# CSR8635-V1_3.net
KiCad netlist of a schematic drawn in EAGLE
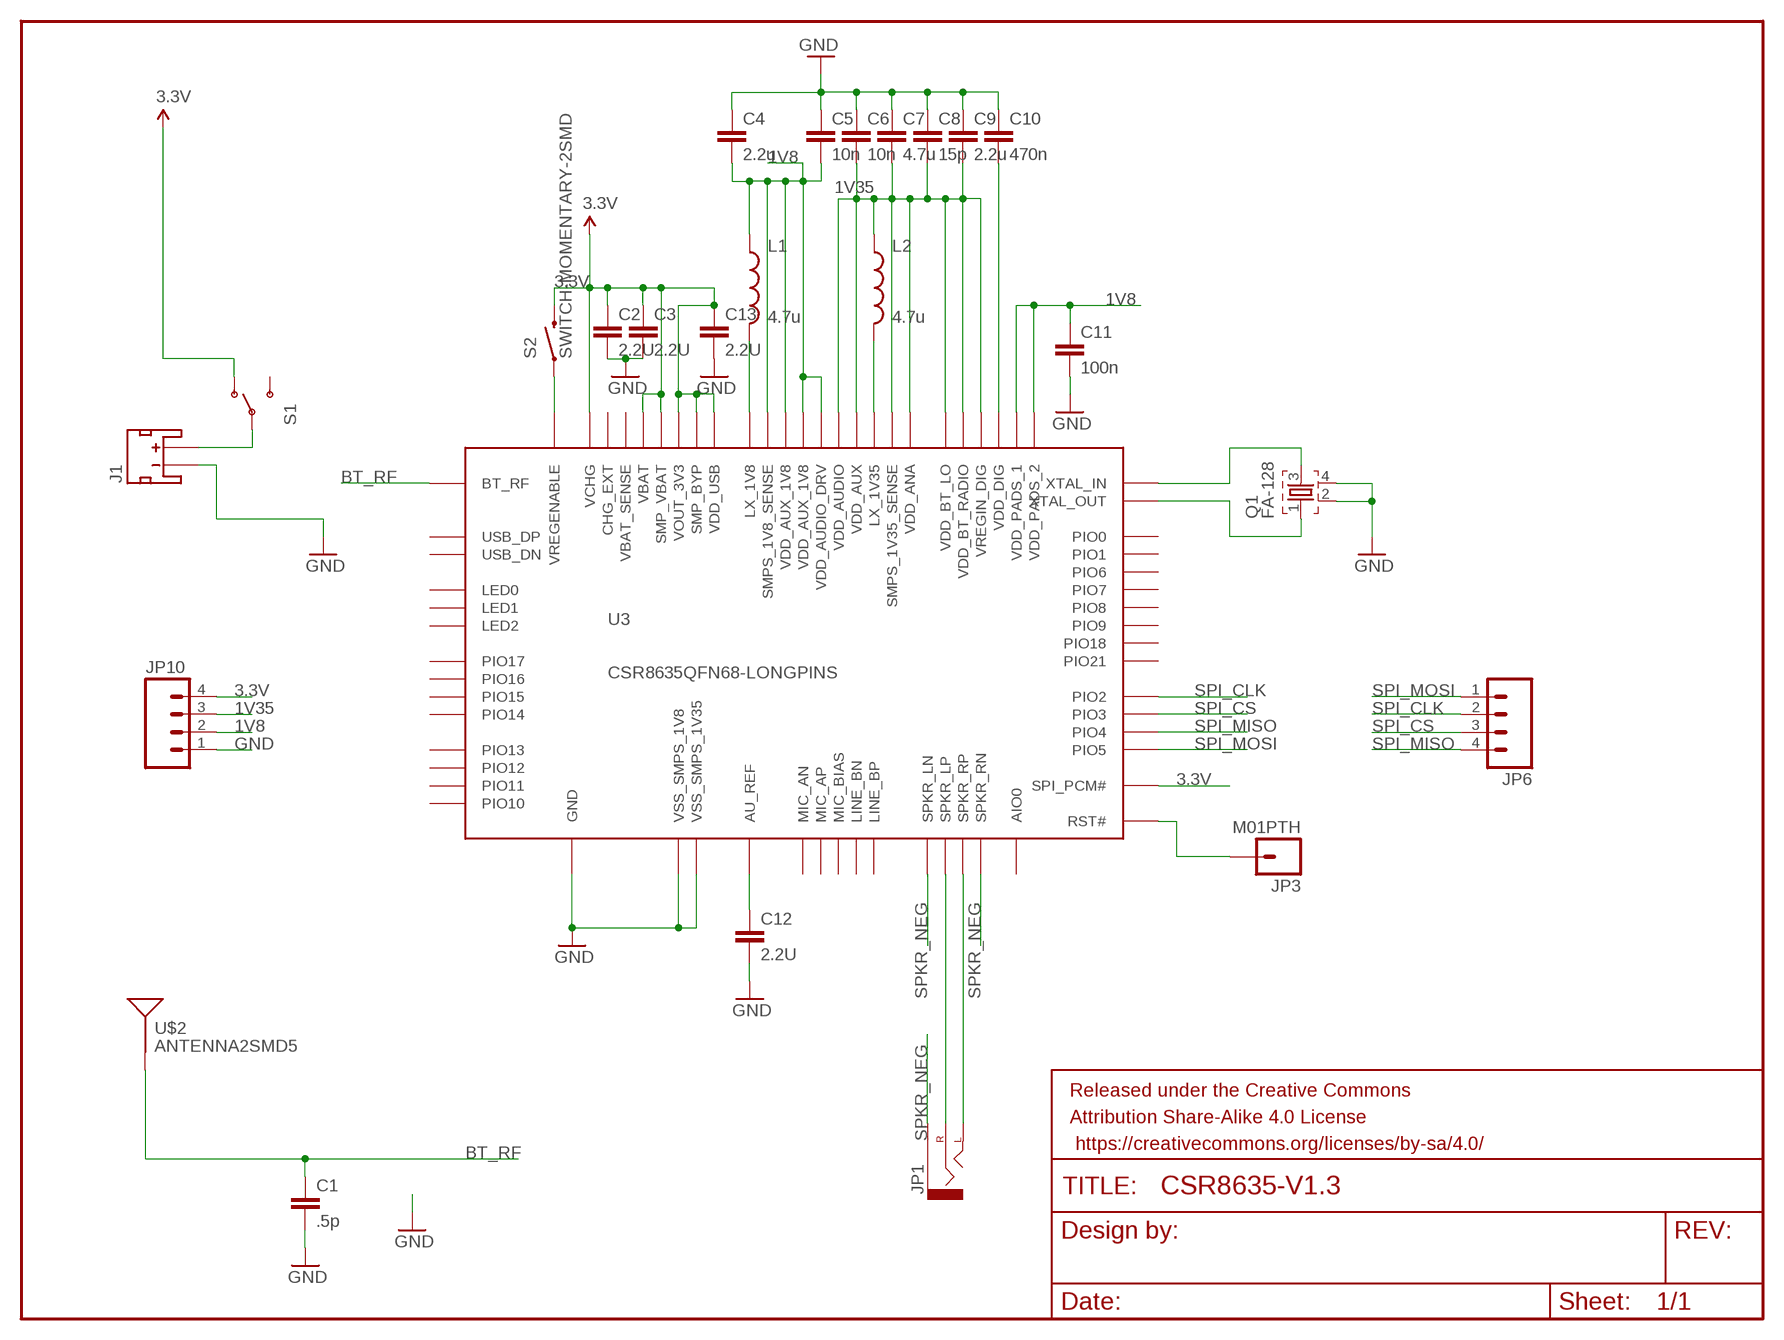
[diagram p0: schematic, sheet 1]

(export (version "E")
  (design (tool "Eeschema 10.0.6"))
  (components
    (comp (ref "C1")
      (value ".5p")
      (footprint "eagle-import:0603-CAP")
      (libsource (lib "eagle-import") (part "CAP0603-CAP"))
    )
    (comp (ref "C2")
      (value "2.2U")
      (footprint "eagle-import:0603-CAP")
      (libsource (lib "eagle-import") (part "CAP0603-CAP"))
    )
    (comp (ref "C3")
      (value "2.2U")
      (footprint "eagle-import:0603-CAP")
      (libsource (lib "eagle-import") (part "CAP0603-CAP"))
    )
    (comp (ref "C4")
      (value "2.2u")
      (footprint "eagle-import:0603-CAP")
      (libsource (lib "eagle-import") (part "CAP0603-CAP"))
    )
    (comp (ref "C5")
      (value "10n")
      (footprint "eagle-import:0603-CAP")
      (libsource (lib "eagle-import") (part "CAP0603-CAP"))
    )
    (comp (ref "C6")
      (value "10n")
      (footprint "eagle-import:0603-CAP")
      (libsource (lib "eagle-import") (part "CAP0603-CAP"))
    )
    (comp (ref "C7")
      (value "4.7u")
      (footprint "eagle-import:0603-CAP")
      (libsource (lib "eagle-import") (part "CAP0603-CAP"))
    )
    (comp (ref "C8")
      (value "15p")
      (footprint "eagle-import:0603-CAP")
      (libsource (lib "eagle-import") (part "CAP0603-CAP"))
    )
    (comp (ref "C9")
      (value "2.2u")
      (footprint "eagle-import:0603-CAP")
      (libsource (lib "eagle-import") (part "CAP0603-CAP"))
    )
    (comp (ref "C10")
      (value "470n")
      (footprint "eagle-import:0603-CAP")
      (libsource (lib "eagle-import") (part "CAP0603-CAP"))
    )
    (comp (ref "C11")
      (value "100n")
      (footprint "eagle-import:0603-CAP")
      (libsource (lib "eagle-import") (part "CAP0603-CAP"))
    )
    (comp (ref "C12")
      (value "2.2U")
      (footprint "eagle-import:0603-CAP")
      (libsource (lib "eagle-import") (part "CAP0603-CAP"))
    )
    (comp (ref "C13")
      (value "2.2U")
      (footprint "eagle-import:0603-CAP")
      (libsource (lib "eagle-import") (part "CAP0603-CAP"))
    )
    (comp (ref "FRAME1")
      (value "FRAME-LETTER")
      (footprint "eagle-import:CREATIVE_COMMONS")
      (libsource (lib "eagle-import") (part "FRAME-LETTER"))
    )
    (comp (ref "J1")
      (value "JST_2MM_MALE")
      (footprint "eagle-import:JST-2-SMD")
      (libsource (lib "eagle-import") (part "JST_2MM_MALE"))
    )
    (comp (ref "JP1")
      (value "AUDIO-JACKSMD2")
      (footprint "eagle-import:AUDIO-JACK-3.5MM-SMD")
      (libsource (lib "eagle-import") (part "AUDIO-JACKSMD2"))
    )
    (comp (ref "JP3")
      (value "M01PTH")
      (footprint "eagle-import:1X01")
      (libsource (lib "eagle-import") (part "M01PTH"))
    )
    (comp (ref "JP6")
      (value "M04PTH")
      (footprint "eagle-import:1X04")
      (libsource (lib "eagle-import") (part "M04PTH"))
    )
    (comp (ref "JP10")
      (value "M04PTH")
      (footprint "eagle-import:1X04")
      (libsource (lib "eagle-import") (part "M04PTH"))
    )
    (comp (ref "L1")
      (value "4.7u")
      (footprint "eagle-import:0805")
      (libsource (lib "eagle-import") (part "INDUCTOR0805"))
    )
    (comp (ref "L2")
      (value "4.7u")
      (footprint "eagle-import:0805")
      (libsource (lib "eagle-import") (part "INDUCTOR0805"))
    )
    (comp (ref "Q1")
      (value "FA-128")
      (footprint "eagle-import:FA-128")
      (libsource (lib "eagle-import") (part "FA-128"))
    )
    (comp (ref "S1")
      (value "SWITCH-SPDTPTH")
      (footprint "eagle-import:SWITCH-SPDT")
      (libsource (lib "eagle-import") (part "SWITCH-SPDTPTH"))
    )
    (comp (ref "S2")
      (value "SWITCH-MOMENTARY-2SMD")
      (footprint "eagle-import:TACTILE-SWITCH-SMD")
      (libsource (lib "eagle-import") (part "SWITCH-MOMENTARY-2SMD"))
    )
    (comp (ref "U$2")
      (value "ANTENNA2SMD5")
      (footprint "eagle-import:ANTENNA-CHIP5")
      (libsource (lib "eagle-import") (part "ANTENNA2SMD5"))
    )
    (comp (ref "U3")
      (value "CSR8635QFN68-LONGPINS")
      (footprint "eagle-import:QFN68")
      (libsource (lib "eagle-import") (part "CSR8635QFN68-LONGPINS"))
    )
  )
  (nets
    (net (code "1") (name "/1V8") (class "Default")
      (node (ref "C11") (pin "1") (pinfunction "1_1") (pintype "passive"))
      (node (ref "C4") (pin "2") (pinfunction "2_2") (pintype "passive"))
      (node (ref "C5") (pin "2") (pinfunction "2_2") (pintype "passive"))
      (node (ref "JP10") (pin "2") (pinfunction "2_2") (pintype "passive"))
      (node (ref "L1") (pin "1") (pinfunction "1_1") (pintype "passive"))
      (node (ref "U3") (pin "15") (pinfunction "VDD_AUX_1V8_15") (pintype "power_in"))
      (node (ref "U3") (pin "16") (pinfunction "VDD_AUX_1V8_16") (pintype "power_in"))
      (node (ref "U3") (pin "33") (pinfunction "VDD_PADS_1_33") (pintype "bidirectional"))
      (node (ref "U3") (pin "53") (pinfunction "SMPS_1V8_SENSE_53") (pintype "bidirectional"))
      (node (ref "U3") (pin "63") (pinfunction "VDD_PADS_2_63") (pintype "power_in"))
      (node (ref "U3") (pin "8") (pinfunction "VDD_AUDIO_DRV_8") (pintype "power_in"))
    )
    (net (code "2") (name "/1V35") (class "Default")
      (node (ref "C6") (pin "2") (pinfunction "2_2") (pintype "passive"))
      (node (ref "C7") (pin "2") (pinfunction "2_2") (pintype "passive"))
      (node (ref "C8") (pin "2") (pinfunction "2_2") (pintype "passive"))
      (node (ref "C9") (pin "2") (pinfunction "2_2") (pintype "passive"))
      (node (ref "JP10") (pin "3") (pinfunction "3_3") (pintype "passive"))
      (node (ref "L2") (pin "1") (pinfunction "1_1") (pintype "passive"))
      (node (ref "U3") (pin "11") (pinfunction "VDD_BT_RADIO_11") (pintype "power_in"))
      (node (ref "U3") (pin "13") (pinfunction "VDD_BT_LO_13") (pintype "power_in"))
      (node (ref "U3") (pin "14") (pinfunction "VDD_AUX_14") (pintype "power_in"))
      (node (ref "U3") (pin "17") (pinfunction "VDD_ANA_17") (pintype "power_in"))
      (node (ref "U3") (pin "3") (pinfunction "VDD_AUDIO_3") (pintype "power_in"))
      (node (ref "U3") (pin "39") (pinfunction "VREGIN_DIG_39") (pintype "bidirectional"))
      (node (ref "U3") (pin "52") (pinfunction "SMPS_1V35_SENSE_52") (pintype "bidirectional"))
    )
    (net (code "3") (name "/BT_RF") (class "Default")
      (node (ref "C1") (pin "1") (pinfunction "1_1") (pintype "passive"))
      (node (ref "U$2") (pin "FEED") (pinfunction "SIGNAL_FEED") (pintype "bidirectional"))
      (node (ref "U3") (pin "12") (pinfunction "BT_RF_12") (pintype "bidirectional"))
    )
    (net (code "4") (name "/SPI_CLK") (class "Default")
      (node (ref "JP6") (pin "2") (pinfunction "2_2") (pintype "passive"))
      (node (ref "U3") (pin "30") (pinfunction "PIO2_30") (pintype "bidirectional"))
    )
    (net (code "5") (name "/SPI_CS") (class "Default")
      (node (ref "JP6") (pin "3") (pinfunction "3_3") (pintype "passive"))
      (node (ref "U3") (pin "28") (pinfunction "PIO3_28") (pintype "bidirectional"))
    )
    (net (code "6") (name "/SPI_MISO") (class "Default")
      (node (ref "JP6") (pin "4") (pinfunction "4_4") (pintype "passive"))
      (node (ref "U3") (pin "24") (pinfunction "PIO4_24") (pintype "bidirectional"))
    )
    (net (code "7") (name "/SPI_MOSI") (class "Default")
      (node (ref "JP6") (pin "1") (pinfunction "1_1") (pintype "passive"))
      (node (ref "U3") (pin "34") (pinfunction "PIO5_34") (pintype "bidirectional"))
    )
    (net (code "8") (name "/SPKR_NEG") (class "Default")
      (node (ref "JP1") (pin "SLEEVE") (pinfunction "SLEEVE_SLEEVE") (pintype "bidirectional"))
      (node (ref "U3") (pin "6") (pinfunction "SPKR_RN_6") (pintype "bidirectional"))
      (node (ref "U3") (pin "9") (pinfunction "SPKR_LN_9") (pintype "bidirectional"))
    )
    (net (code "9") (name "3.3V") (class "Default")
      (node (ref "C13") (pin "1") (pinfunction "1_1") (pintype "passive"))
      (node (ref "C2") (pin "1") (pinfunction "1_1") (pintype "passive"))
      (node (ref "C3") (pin "1") (pinfunction "1_1") (pintype "passive"))
      (node (ref "JP10") (pin "4") (pinfunction "4_4") (pintype "passive"))
      (node (ref "S1") (pin "1") (pinfunction "O_1") (pintype "passive"))
      (node (ref "S2") (pin "3") (pinfunction "2_3") (pintype "passive"))
      (node (ref "U3") (pin "29") (pinfunction "SPI_PCM#_29") (pintype "bidirectional"))
      (node (ref "U3") (pin "41") (pinfunction "VOUT_3V3_41") (pintype "power_in"))
      (node (ref "U3") (pin "42") (pinfunction "VCHG_42") (pintype "bidirectional"))
      (node (ref "U3") (pin "45") (pinfunction "VBAT_45") (pintype "power_in"))
      (node (ref "U3") (pin "48") (pinfunction "SMP_VBAT_48") (pintype "bidirectional"))
      (node (ref "U3") (pin "49") (pinfunction "SMP_BYP_49") (pintype "bidirectional"))
      (node (ref "U3") (pin "54") (pinfunction "VDD_USB_54") (pintype "power_in"))
    )
    (net (code "10") (name "GND") (class "Default")
      (node (ref "C1") (pin "2") (pinfunction "2_2") (pintype "passive"))
      (node (ref "C10") (pin "1") (pinfunction "1_1") (pintype "passive"))
      (node (ref "C11") (pin "2") (pinfunction "2_2") (pintype "passive"))
      (node (ref "C12") (pin "2") (pinfunction "2_2") (pintype "passive"))
      (node (ref "C13") (pin "2") (pinfunction "2_2") (pintype "passive"))
      (node (ref "C2") (pin "2") (pinfunction "2_2") (pintype "passive"))
      (node (ref "C3") (pin "2") (pinfunction "2_2") (pintype "passive"))
      (node (ref "C4") (pin "1") (pinfunction "1_1") (pintype "passive"))
      (node (ref "C5") (pin "1") (pinfunction "1_1") (pintype "passive"))
      (node (ref "C6") (pin "1") (pinfunction "1_1") (pintype "passive"))
      (node (ref "C7") (pin "1") (pinfunction "1_1") (pintype "passive"))
      (node (ref "C8") (pin "1") (pinfunction "1_1") (pintype "passive"))
      (node (ref "C9") (pin "1") (pinfunction "1_1") (pintype "passive"))
      (node (ref "J1") (pin "1") (pinfunction "-_1") (pintype "bidirectional"))
      (node (ref "JP10") (pin "1") (pinfunction "1_1") (pintype "passive"))
      (node (ref "Q1") (pin "2") (pinfunction "2_2") (pintype "passive"))
      (node (ref "Q1") (pin "4") (pinfunction "4_4") (pintype "passive"))
      (node (ref "U3") (pin "46") (pinfunction "VSS_SMPS_1V8_46") (pintype "bidirectional"))
      (node (ref "U3") (pin "51") (pinfunction "VSS_SMPS_1V35_51") (pintype "bidirectional"))
      (node (ref "U3") (pin "CNTR") (pinfunction "GND_CNTR") (pintype "bidirectional"))
      (node (ref "U3") (pin "CNTR1") (pinfunction "GND_CNTR1") (pintype "bidirectional"))
      (node (ref "U3") (pin "CNTR2") (pinfunction "GND_CNTR2") (pintype "bidirectional"))
      (node (ref "U3") (pin "CNTR3") (pinfunction "GND_CNTR3") (pintype "bidirectional"))
    )
    (net (code "11") (name "Net-(J1-+)") (class "Default")
      (node (ref "J1") (pin "2") (pinfunction "+_2") (pintype "bidirectional"))
      (node (ref "S1") (pin "2") (pinfunction "P_2") (pintype "passive"))
    )
    (net (code "12") (name "Net-(JP1-LEFT)") (class "Default")
      (node (ref "JP1") (pin "TIP") (pinfunction "LEFT_TIP") (pintype "bidirectional"))
      (node (ref "U3") (pin "7") (pinfunction "SPKR_RP_7") (pintype "bidirectional"))
    )
    (net (code "13") (name "Net-(JP1-RIGHT)") (class "Default")
      (node (ref "JP1") (pin "RING") (pinfunction "RIGHT_RING") (pintype "bidirectional"))
      (node (ref "U3") (pin "10") (pinfunction "SPKR_LP_10") (pintype "bidirectional"))
    )
    (net (code "14") (name "Net-(U3-AU_REF)") (class "Default")
      (node (ref "C12") (pin "1") (pinfunction "1_1") (pintype "passive"))
      (node (ref "U3") (pin "1") (pinfunction "AU_REF_1") (pintype "bidirectional"))
    )
    (net (code "15") (name "Net-(U3-LX_1V8)") (class "Default")
      (node (ref "L1") (pin "2") (pinfunction "2_2") (pintype "passive"))
      (node (ref "U3") (pin "47") (pinfunction "LX_1V8_47") (pintype "bidirectional"))
    )
    (net (code "16") (name "Net-(U3-LX_1V35)") (class "Default")
      (node (ref "L2") (pin "2") (pinfunction "2_2") (pintype "passive"))
      (node (ref "U3") (pin "50") (pinfunction "LX_1V35_50") (pintype "bidirectional"))
    )
    (net (code "17") (name "Net-(U3-RST#)") (class "Default")
      (node (ref "JP3") (pin "1") (pinfunction "1_1") (pintype "passive"))
      (node (ref "U3") (pin "35") (pinfunction "RST#_35") (pintype "bidirectional"))
    )
    (net (code "18") (name "Net-(U3-VDD_DIG)") (class "Default")
      (node (ref "C10") (pin "2") (pinfunction "2_2") (pintype "passive"))
      (node (ref "U3") (pin "38") (pinfunction "VDD_DIG_38") (pintype "power_in"))
    )
    (net (code "19") (name "Net-(U3-VREGENABLE)") (class "Default")
      (node (ref "S2") (pin "1") (pinfunction "1_1") (pintype "passive"))
      (node (ref "U3") (pin "40") (pinfunction "VREGENABLE_40") (pintype "bidirectional"))
    )
    (net (code "20") (name "Net-(U3-XTAL_IN)") (class "Default")
      (node (ref "Q1") (pin "3") (pinfunction "3_3") (pintype "passive"))
      (node (ref "U3") (pin "19") (pinfunction "XTAL_IN_19") (pintype "bidirectional"))
    )
    (net (code "21") (name "Net-(U3-XTAL_OUT)") (class "Default")
      (node (ref "Q1") (pin "1") (pinfunction "1_1") (pintype "passive"))
      (node (ref "U3") (pin "18") (pinfunction "XTAL_OUT_18") (pintype "bidirectional"))
    )
    (net (code "22") (name "unconnected-(J1-PAD1-PadNC1)") (class "Default")
      (node (ref "J1") (pin "NC1") (pinfunction "PAD1_NC1") (pintype "bidirectional"))
    )
    (net (code "23") (name "unconnected-(J1-PAD2-PadNC2)") (class "Default")
      (node (ref "J1") (pin "NC2") (pinfunction "PAD2_NC2") (pintype "bidirectional"))
    )
    (net (code "24") (name "unconnected-(S1-S-Pad3)") (class "Default")
      (node (ref "S1") (pin "3") (pinfunction "S_3") (pintype "passive"))
    )
    (net (code "25") (name "unconnected-(U3-AIO0-Pad20)") (class "Default")
      (node (ref "U3") (pin "20") (pinfunction "AIO0_20") (pintype "bidirectional"))
    )
    (net (code "26") (name "unconnected-(U3-CHG_EXT-Pad43)") (class "Default")
      (node (ref "U3") (pin "43") (pinfunction "CHG_EXT_43") (pintype "bidirectional"))
    )
    (net (code "27") (name "unconnected-(U3-LED0-Pad37)") (class "Default")
      (node (ref "U3") (pin "37") (pinfunction "LED0_37") (pintype "bidirectional"))
    )
    (net (code "28") (name "unconnected-(U3-LED1-Pad36)") (class "Default")
      (node (ref "U3") (pin "36") (pinfunction "LED1_36") (pintype "bidirectional"))
    )
    (net (code "29") (name "unconnected-(U3-LED2-Pad66)") (class "Default")
      (node (ref "U3") (pin "66") (pinfunction "LED2_66") (pintype "bidirectional"))
    )
    (net (code "30") (name "unconnected-(U3-LINE_BN-Pad4)") (class "Default")
      (node (ref "U3") (pin "4") (pinfunction "LINE_BN_4") (pintype "bidirectional"))
    )
    (net (code "31") (name "unconnected-(U3-LINE_BP-Pad5)") (class "Default")
      (node (ref "U3") (pin "5") (pinfunction "LINE_BP_5") (pintype "bidirectional"))
    )
    (net (code "32") (name "unconnected-(U3-MIC_AN-Pad67)") (class "Default")
      (node (ref "U3") (pin "67") (pinfunction "MIC_AN_67") (pintype "bidirectional"))
    )
    (net (code "33") (name "unconnected-(U3-MIC_AP-Pad68)") (class "Default")
      (node (ref "U3") (pin "68") (pinfunction "MIC_AP_68") (pintype "bidirectional"))
    )
    (net (code "34") (name "unconnected-(U3-MIC_BIAS-Pad2)") (class "Default")
      (node (ref "U3") (pin "2") (pinfunction "MIC_BIAS_2") (pintype "bidirectional"))
    )
    (net (code "35") (name "unconnected-(U3-PIO0-Pad59)") (class "Default")
      (node (ref "U3") (pin "59") (pinfunction "PIO0_59") (pintype "bidirectional"))
    )
    (net (code "36") (name "unconnected-(U3-PIO1-Pad60)") (class "Default")
      (node (ref "U3") (pin "60") (pinfunction "PIO1_60") (pintype "bidirectional"))
    )
    (net (code "37") (name "unconnected-(U3-PIO6-Pad62)") (class "Default")
      (node (ref "U3") (pin "62") (pinfunction "PIO6_62") (pintype "bidirectional"))
    )
    (net (code "38") (name "unconnected-(U3-PIO7-Pad57)") (class "Default")
      (node (ref "U3") (pin "57") (pinfunction "PIO7_57") (pintype "bidirectional"))
    )
    (net (code "39") (name "unconnected-(U3-PIO8-Pad61)") (class "Default")
      (node (ref "U3") (pin "61") (pinfunction "PIO8_61") (pintype "bidirectional"))
    )
    (net (code "40") (name "unconnected-(U3-PIO9-Pad58)") (class "Default")
      (node (ref "U3") (pin "58") (pinfunction "PIO9_58") (pintype "bidirectional"))
    )
    (net (code "41") (name "unconnected-(U3-PIO10-Pad25)") (class "Default")
      (node (ref "U3") (pin "25") (pinfunction "PIO10_25") (pintype "bidirectional"))
    )
    (net (code "42") (name "unconnected-(U3-PIO11-Pad26)") (class "Default")
      (node (ref "U3") (pin "26") (pinfunction "PIO11_26") (pintype "bidirectional"))
    )
    (net (code "43") (name "unconnected-(U3-PIO12-Pad22)") (class "Default")
      (node (ref "U3") (pin "22") (pinfunction "PIO12_22") (pintype "bidirectional"))
    )
    (net (code "44") (name "unconnected-(U3-PIO13-Pad31)") (class "Default")
      (node (ref "U3") (pin "31") (pinfunction "PIO13_31") (pintype "bidirectional"))
    )
    (net (code "45") (name "unconnected-(U3-PIO14-Pad23)") (class "Default")
      (node (ref "U3") (pin "23") (pinfunction "PIO14_23") (pintype "bidirectional"))
    )
    (net (code "46") (name "unconnected-(U3-PIO15-Pad21)") (class "Default")
      (node (ref "U3") (pin "21") (pinfunction "PIO15_21") (pintype "bidirectional"))
    )
    (net (code "47") (name "unconnected-(U3-PIO16-Pad27)") (class "Default")
      (node (ref "U3") (pin "27") (pinfunction "PIO16_27") (pintype "bidirectional"))
    )
    (net (code "48") (name "unconnected-(U3-PIO17-Pad32)") (class "Default")
      (node (ref "U3") (pin "32") (pinfunction "PIO17_32") (pintype "bidirectional"))
    )
    (net (code "49") (name "unconnected-(U3-PIO18-Pad65)") (class "Default")
      (node (ref "U3") (pin "65") (pinfunction "PIO18_65") (pintype "bidirectional"))
    )
    (net (code "50") (name "unconnected-(U3-PIO21-Pad64)") (class "Default")
      (node (ref "U3") (pin "64") (pinfunction "PIO21_64") (pintype "bidirectional"))
    )
    (net (code "51") (name "unconnected-(U3-USB_DN-Pad55)") (class "Default")
      (node (ref "U3") (pin "55") (pinfunction "USB_DN_55") (pintype "bidirectional"))
    )
    (net (code "52") (name "unconnected-(U3-USB_DP-Pad56)") (class "Default")
      (node (ref "U3") (pin "56") (pinfunction "USB_DP_56") (pintype "bidirectional"))
    )
    (net (code "53") (name "unconnected-(U3-VBAT_SENSE-Pad44)") (class "Default")
      (node (ref "U3") (pin "44") (pinfunction "VBAT_SENSE_44") (pintype "bidirectional"))
    )
  )
)
